# Rx_Nano_V2-1.net
KiCad netlist of a schematic drawn in EAGLE
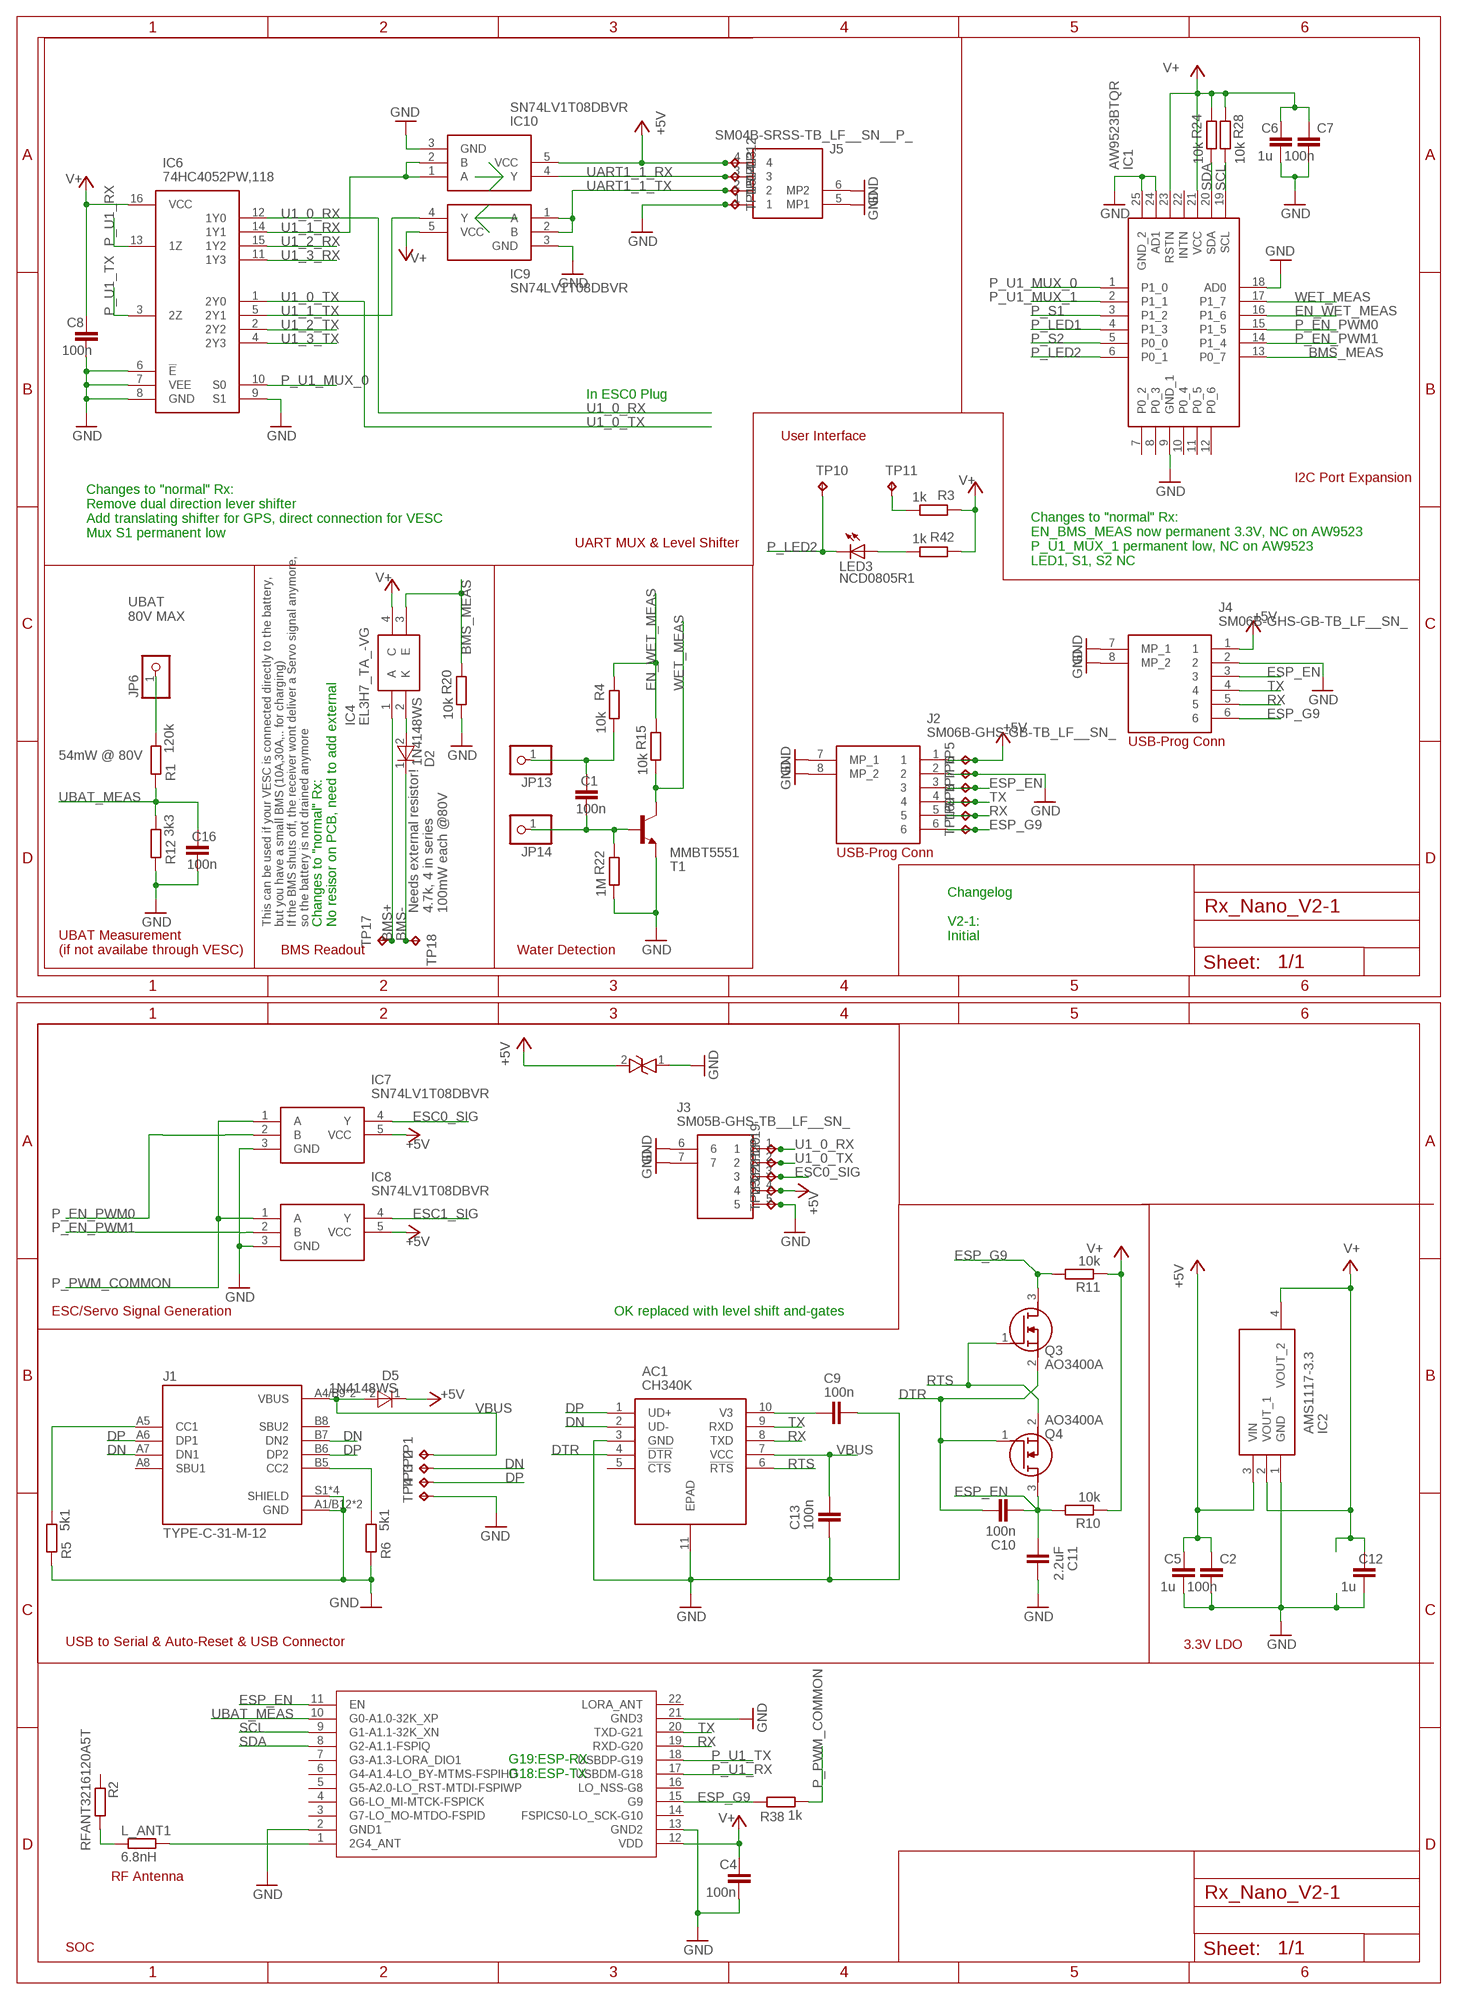
[diagram p0: schematic, sheet 1, part 1 of 2]
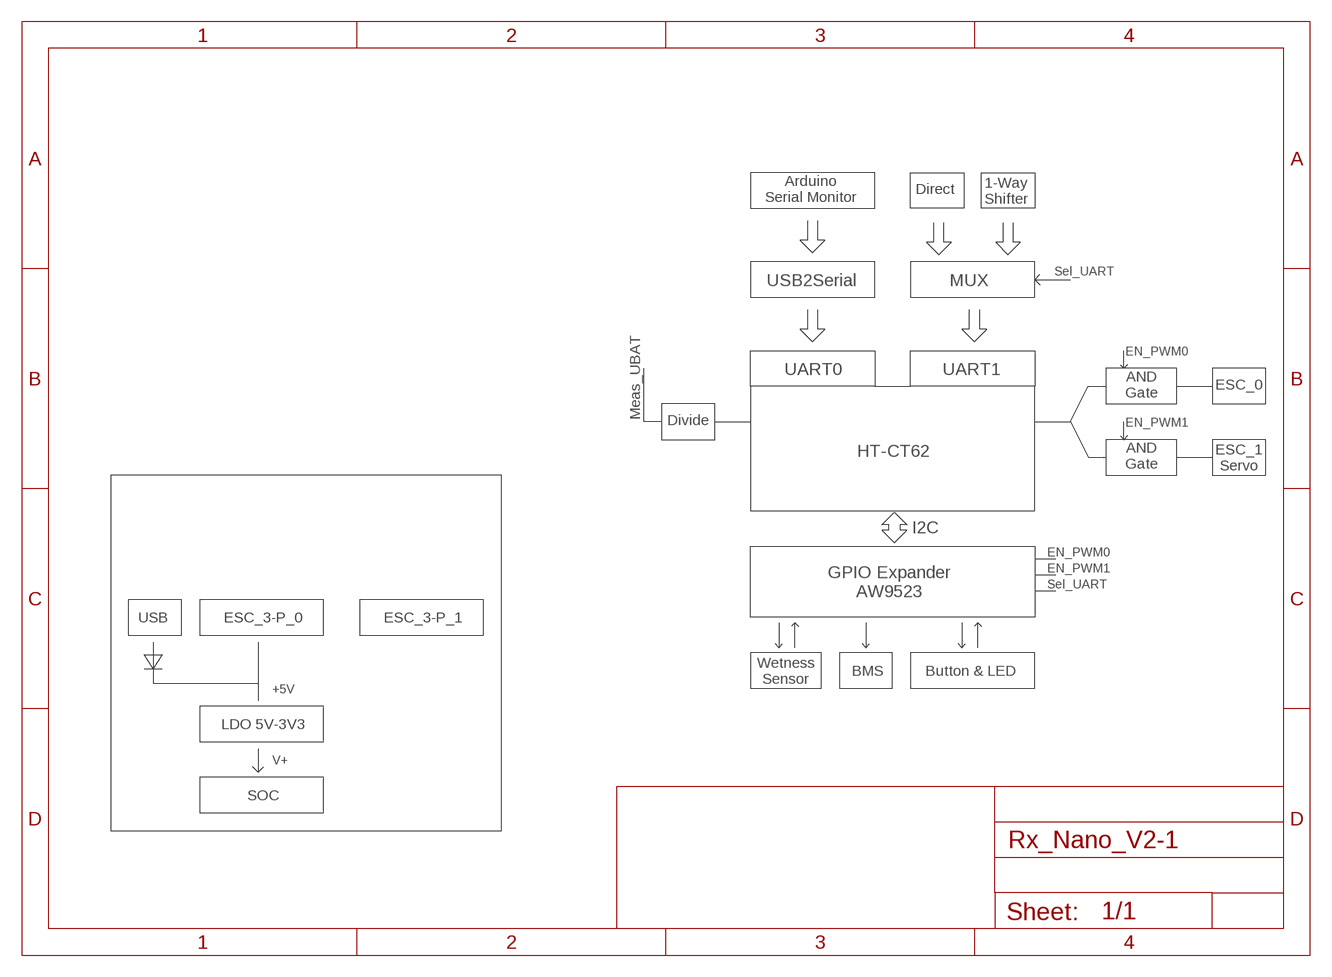
[diagram p1: schematic, sheet 1, part 2 of 2]

(export (version "E")
  (design (tool "Eeschema 10.0.6"))
  (components
    (comp (ref "AC1")
      (value "CH340K")
      (footprint "eagle-import:SOP100P600X180-11N")
      (libsource (lib "eagle-import") (part "CH340K"))
    )
    (comp (ref "C1")
      (value "100n")
      (footprint "eagle-import:C0402")
      (libsource (lib "eagle-import") (part "C-EUC0402"))
    )
    (comp (ref "C2")
      (value "100n")
      (footprint "eagle-import:C0402")
      (libsource (lib "eagle-import") (part "C-EUC0402"))
    )
    (comp (ref "C4")
      (value "100n")
      (footprint "eagle-import:C0402")
      (libsource (lib "eagle-import") (part "C-EUC0402"))
    )
    (comp (ref "C5")
      (value "1u")
      (footprint "eagle-import:C0603")
      (libsource (lib "eagle-import") (part "C-EUC0603"))
    )
    (comp (ref "C6")
      (value "1u")
      (footprint "eagle-import:C0603")
      (libsource (lib "eagle-import") (part "C-EUC0603"))
    )
    (comp (ref "C7")
      (value "100n")
      (footprint "eagle-import:C0402")
      (libsource (lib "eagle-import") (part "C-EUC0402"))
    )
    (comp (ref "C8")
      (value "100n")
      (footprint "eagle-import:C0402")
      (libsource (lib "eagle-import") (part "C-EUC0402"))
    )
    (comp (ref "C9")
      (value "100n")
      (footprint "eagle-import:C0402")
      (libsource (lib "eagle-import") (part "C-EUC0402"))
    )
    (comp (ref "C10")
      (value "100n")
      (footprint "eagle-import:C0402")
      (libsource (lib "eagle-import") (part "C-EUC0402"))
    )
    (comp (ref "C11")
      (value "2.2uF")
      (footprint "eagle-import:C0603")
      (libsource (lib "eagle-import") (part "C-EUC0603"))
    )
    (comp (ref "C12")
      (value "1u")
      (footprint "eagle-import:C0603")
      (libsource (lib "eagle-import") (part "C-EUC0603"))
    )
    (comp (ref "C13")
      (value "100n")
      (footprint "eagle-import:C0402")
      (libsource (lib "eagle-import") (part "C-EUC0402"))
    )
    (comp (ref "C16")
      (value "100n")
      (footprint "eagle-import:C0402")
      (libsource (lib "eagle-import") (part "C-EUC0402"))
    )
    (comp (ref "D2")
      (value "1N4148WS")
      (footprint "eagle-import:SODFL2512X90N")
      (fields (field (name "MOUSER_PART_NUMBER") "512-1N4148WS"))
      (libsource (lib "eagle-import") (part "1N4148WS"))
    )
    (comp (ref "D4")
      (value "P6SMB6.8CA")
      (footprint "eagle-import:DIONM5436X261N")
      (fields (field (name "MOUSER_PART_NUMBER") "576-P6SMB6.8CA"))
      (libsource (lib "eagle-import") (part "P6SMB6.8CA"))
    )
    (comp (ref "D5")
      (value "1N4148WS")
      (footprint "eagle-import:SODFL2512X90N")
      (fields (field (name "MOUSER_PART_NUMBER") "512-1N4148WS"))
      (libsource (lib "eagle-import") (part "1N4148WS"))
    )
    (comp (ref "IC1")
      (value "AW9523BTQR")
      (footprint "eagle-import:QFN50P400X400X80-25N")
      (libsource (lib "eagle-import") (part "AW9523BTQR"))
    )
    (comp (ref "IC2")
      (value "AMS1117-3.3")
      (footprint "eagle-import:SOT229P700X180-4N")
      (libsource (lib "eagle-import") (part "AMS1117-3.3"))
    )
    (comp (ref "IC4")
      (value "EL3H7_TA_-VG")
      (footprint "eagle-import:SOIC127P700X200-4N")
      (fields
        (field (name "ARROW_PART_NUMBER") "EL3H7(TA)-VG")
        (field (name "MOUSER_PART_NUMBER") "638-EL3H7TAVG")
      )
      (libsource (lib "eagle-import") (part "EL3H7_TA_-VG"))
    )
    (comp (ref "IC6")
      (value "74HC4052PW,118")
      (footprint "eagle-import:SOP65P640X110-16N")
      (fields (field (name "MOUSER_PART_NUMBER") "771-74HC4052PW-T"))
      (libsource (lib "eagle-import") (part "74HC4052PW,118"))
    )
    (comp (ref "IC7")
      (value "SN74LV1T08DBVR")
      (footprint "eagle-import:SOT95P280X145-5N")
      (fields (field (name "MOUSER_PART_NUMBER") "595-SN74LV1T08DBVR"))
      (libsource (lib "eagle-import") (part "SN74LV1T08DBVR"))
    )
    (comp (ref "IC8")
      (value "SN74LV1T08DBVR")
      (footprint "eagle-import:SOT95P280X145-5N")
      (fields (field (name "MOUSER_PART_NUMBER") "595-SN74LV1T08DBVR"))
      (libsource (lib "eagle-import") (part "SN74LV1T08DBVR"))
    )
    (comp (ref "IC9")
      (value "SN74LV1T08DBVR")
      (footprint "eagle-import:SOT95P280X145-5N")
      (fields (field (name "MOUSER_PART_NUMBER") "595-SN74LV1T08DBVR"))
      (libsource (lib "eagle-import") (part "SN74LV1T08DBVR"))
    )
    (comp (ref "IC10")
      (value "SN74LV1T08DBVR")
      (footprint "eagle-import:SOT95P280X145-5N")
      (fields (field (name "MOUSER_PART_NUMBER") "595-SN74LV1T08DBVR"))
      (libsource (lib "eagle-import") (part "SN74LV1T08DBVR"))
    )
    (comp (ref "J1")
      (value "TYPE-C-31-M-12")
      (footprint "eagle-import:HRO_TYPE-C-31-M-12")
      (fields (field (name "MF") "HRO Electronics Co., Ltd."))
      (libsource (lib "eagle-import") (part "TYPE-C-31-M-12"))
    )
    (comp (ref "J2")
      (value "SM06B-GHS-GB-TB_LF__SN_")
      (footprint "eagle-import:SM06BGHSGBTBLFSN")
      (fields
        (field (name "MANUFACTURER_PART_NUMBER") "SM06B-GHS-GB-TB(LF)(SN)")
        (field (name "MOUSER_PART_NUMBER") "306-SM06BGHSGBTBLFSN")
      )
      (libsource (lib "eagle-import") (part "SM06B-GHS-GB-TB_LF__SN_"))
    )
    (comp (ref "J3")
      (value "SM05B-GHS-TB__LF__SN_")
      (footprint "eagle-import:SM05BGHSTBLFSN")
      (fields (field (name "MANUFACTURER_PART_NUMBER") "SM05B-GHS-TB (LF)(SN)"))
      (libsource (lib "eagle-import") (part "SM05B-GHS-TB__LF__SN_"))
    )
    (comp (ref "J4")
      (value "SM06B-GHS-GB-TB_LF__SN_")
      (footprint "eagle-import:SM06BGHSGBTBLFSN")
      (fields
        (field (name "MANUFACTURER_PART_NUMBER") "SM06B-GHS-GB-TB(LF)(SN)")
        (field (name "MOUSER_PART_NUMBER") "306-SM06BGHSGBTBLFSN")
      )
      (libsource (lib "eagle-import") (part "SM06B-GHS-GB-TB_LF__SN_"))
    )
    (comp (ref "J5")
      (value "SM04B-SRSS-TB_LF__SN__P_")
      (footprint "eagle-import:SM04BSRSSTBLFSNP")
      (fields
        (field (name "MANUFACTURER_PART_NUMBER") "SM04B-SRSS-TB(LF)(SN)(P)")
        (field (name "MOUSER_PART_NUMBER") "306-SM04BSRSSTBLFSNP")
      )
      (libsource (lib "eagle-import") (part "SM04B-SRSS-TB_LF__SN__P_"))
    )
    (comp (ref "JP6")
      (value "PINHD-1X1")
      (footprint "eagle-import:1X01")
      (libsource (lib "eagle-import") (part "PINHD-1X1"))
    )
    (comp (ref "JP13")
      (value "PINHD-1X1")
      (footprint "eagle-import:1X01")
      (libsource (lib "eagle-import") (part "PINHD-1X1"))
    )
    (comp (ref "JP14")
      (value "PINHD-1X1")
      (footprint "eagle-import:1X01")
      (libsource (lib "eagle-import") (part "PINHD-1X1"))
    )
    (comp (ref "LED3")
      (value "NCD0805R1")
      (footprint "eagle-import:CHIP-LED0603")
      (libsource (lib "eagle-import") (part "LEDCHIP-LED0603"))
    )
    (comp (ref "L_ANT1")
      (value "6.8nH")
      (footprint "eagle-import:R0402")
      (libsource (lib "eagle-import") (part "R-EU_R0402"))
    )
    (comp (ref "Q3")
      (value "AO3400A")
      (footprint "eagle-import:SOT95P280X125-3N")
      (libsource (lib "eagle-import") (part "AO3400A"))
    )
    (comp (ref "Q4")
      (value "AO3400A")
      (footprint "eagle-import:SOT95P280X125-3N")
      (libsource (lib "eagle-import") (part "AO3400A"))
    )
    (comp (ref "R1")
      (value "120k")
      (footprint "eagle-import:R0603")
      (libsource (lib "eagle-import") (part "R-EU_R0603"))
    )
    (comp (ref "R2")
      (value "RFANT3216120A5T")
      (footprint "eagle-import:R1206")
      (libsource (lib "eagle-import") (part "R-EU_R1206"))
    )
    (comp (ref "R3")
      (value "1k")
      (footprint "eagle-import:R0402")
      (libsource (lib "eagle-import") (part "R-EU_R0402"))
    )
    (comp (ref "R4")
      (value "10k")
      (footprint "eagle-import:R0402")
      (libsource (lib "eagle-import") (part "R-EU_R0402"))
    )
    (comp (ref "R5")
      (value "5k1")
      (footprint "eagle-import:R0402")
      (libsource (lib "eagle-import") (part "R-EU_R0402"))
    )
    (comp (ref "R6")
      (value "5k1")
      (footprint "eagle-import:R0402")
      (libsource (lib "eagle-import") (part "R-EU_R0402"))
    )
    (comp (ref "R10")
      (value "10k")
      (footprint "eagle-import:R0402")
      (libsource (lib "eagle-import") (part "R-EU_R0402"))
    )
    (comp (ref "R11")
      (value "10k")
      (footprint "eagle-import:R0402")
      (libsource (lib "eagle-import") (part "R-EU_R0402"))
    )
    (comp (ref "R12")
      (value "3k3")
      (footprint "eagle-import:R0402")
      (libsource (lib "eagle-import") (part "R-EU_R0402"))
    )
    (comp (ref "R15")
      (value "10k")
      (footprint "eagle-import:R0402")
      (libsource (lib "eagle-import") (part "R-EU_R0402"))
    )
    (comp (ref "R20")
      (value "10k")
      (footprint "eagle-import:R0402")
      (libsource (lib "eagle-import") (part "R-EU_R0402"))
    )
    (comp (ref "R22")
      (value "1M")
      (footprint "eagle-import:R0402")
      (libsource (lib "eagle-import") (part "R-EU_R0402"))
    )
    (comp (ref "R24")
      (value "10k")
      (footprint "eagle-import:R0402")
      (libsource (lib "eagle-import") (part "R-EU_R0402"))
    )
    (comp (ref "R28")
      (value "10k")
      (footprint "eagle-import:R0402")
      (libsource (lib "eagle-import") (part "R-EU_R0402"))
    )
    (comp (ref "R38")
      (value "1k")
      (footprint "eagle-import:R0402")
      (libsource (lib "eagle-import") (part "R-EU_R0402"))
    )
    (comp (ref "R42")
      (value "1k")
      (footprint "eagle-import:R0402")
      (libsource (lib "eagle-import") (part "R-EU_R0402"))
    )
    (comp (ref "T1")
      (value "MMBT5551")
      (footprint "eagle-import:SOT23-BEC")
      (libsource (lib "eagle-import") (part "-NPN-SOT23-BECBC847B"))
    )
    (comp (ref "TP1")
      (value "TPB1,27")
      (footprint "eagle-import:B1,27")
      (libsource (lib "eagle-import") (part "TPB1,27"))
    )
    (comp (ref "TP2")
      (value "TPB1,27")
      (footprint "eagle-import:B1,27")
      (libsource (lib "eagle-import") (part "TPB1,27"))
    )
    (comp (ref "TP3")
      (value "TPB1,27")
      (footprint "eagle-import:B1,27")
      (libsource (lib "eagle-import") (part "TPB1,27"))
    )
    (comp (ref "TP4")
      (value "TPB1,27")
      (footprint "eagle-import:B1,27")
      (libsource (lib "eagle-import") (part "TPB1,27"))
    )
    (comp (ref "TP5")
      (value "TPB1,27")
      (footprint "eagle-import:B1,27")
      (libsource (lib "eagle-import") (part "TPB1,27"))
    )
    (comp (ref "TP6")
      (value "TPB1,27")
      (footprint "eagle-import:B1,27")
      (libsource (lib "eagle-import") (part "TPB1,27"))
    )
    (comp (ref "TP7")
      (value "TPB1,27")
      (footprint "eagle-import:B1,27")
      (libsource (lib "eagle-import") (part "TPB1,27"))
    )
    (comp (ref "TP8")
      (value "TPB1,27")
      (footprint "eagle-import:B1,27")
      (libsource (lib "eagle-import") (part "TPB1,27"))
    )
    (comp (ref "TP9")
      (value "TPB1,27")
      (footprint "eagle-import:B1,27")
      (libsource (lib "eagle-import") (part "TPB1,27"))
    )
    (comp (ref "TP10")
      (value "TPB1,27")
      (footprint "eagle-import:B1,27")
      (libsource (lib "eagle-import") (part "TPB1,27"))
    )
    (comp (ref "TP11")
      (value "TPB1,27")
      (footprint "eagle-import:B1,27")
      (libsource (lib "eagle-import") (part "TPB1,27"))
    )
    (comp (ref "TP12")
      (value "TPB1,27")
      (footprint "eagle-import:B1,27")
      (libsource (lib "eagle-import") (part "TPB1,27"))
    )
    (comp (ref "TP13")
      (value "TPB1,27")
      (footprint "eagle-import:B1,27")
      (libsource (lib "eagle-import") (part "TPB1,27"))
    )
    (comp (ref "TP14")
      (value "TPB1,27")
      (footprint "eagle-import:B1,27")
      (libsource (lib "eagle-import") (part "TPB1,27"))
    )
    (comp (ref "TP15")
      (value "TPB1,27")
      (footprint "eagle-import:B1,27")
      (libsource (lib "eagle-import") (part "TPB1,27"))
    )
    (comp (ref "TP16")
      (value "TPB1,27")
      (footprint "eagle-import:B1,27")
      (libsource (lib "eagle-import") (part "TPB1,27"))
    )
    (comp (ref "TP17")
      (value "TPB1,27")
      (footprint "eagle-import:B1,27")
      (libsource (lib "eagle-import") (part "TPB1,27"))
    )
    (comp (ref "TP18")
      (value "TPB1,27")
      (footprint "eagle-import:B1,27")
      (libsource (lib "eagle-import") (part "TPB1,27"))
    )
    (comp (ref "TP19")
      (value "TPB1,27")
      (footprint "eagle-import:B1,27")
      (libsource (lib "eagle-import") (part "TPB1,27"))
    )
    (comp (ref "TP20")
      (value "TPB1,27")
      (footprint "eagle-import:B1,27")
      (libsource (lib "eagle-import") (part "TPB1,27"))
    )
    (comp (ref "TP21")
      (value "TPB1,27")
      (footprint "eagle-import:B1,27")
      (libsource (lib "eagle-import") (part "TPB1,27"))
    )
    (comp (ref "TP22")
      (value "TPB1,27")
      (footprint "eagle-import:B1,27")
      (libsource (lib "eagle-import") (part "TPB1,27"))
    )
    (comp (ref "TP23")
      (value "TPB1,27")
      (footprint "eagle-import:B1,27")
      (libsource (lib "eagle-import") (part "TPB1,27"))
    )
    (comp (ref "U$5")
      (value "HT-CT62")
      (footprint "eagle-import:HT-CT62")
      (libsource (lib "eagle-import") (part "HT-CT62"))
    )
  )
  (nets
    (net (code "1") (name "+5V") (class "Default")
      (node (ref "C2") (pin "1") (pinfunction "1_1") (pintype "passive"))
      (node (ref "C5") (pin "1") (pinfunction "1_1") (pintype "passive"))
      (node (ref "D4") (pin "2") (pinfunction "2_2") (pintype "bidirectional"))
      (node (ref "D5") (pin "1") (pinfunction "K_1") (pintype "bidirectional"))
      (node (ref "IC10") (pin "5") (pinfunction "VCC_5") (pintype "power_in"))
      (node (ref "IC2") (pin "3") (pinfunction "VIN_3") (pintype "bidirectional"))
      (node (ref "IC7") (pin "5") (pinfunction "VCC_5") (pintype "power_in"))
      (node (ref "IC8") (pin "5") (pinfunction "VCC_5") (pintype "power_in"))
      (node (ref "J2") (pin "1") (pinfunction "1_1") (pintype "bidirectional"))
      (node (ref "J3") (pin "4") (pinfunction "4_4") (pintype "bidirectional"))
      (node (ref "J4") (pin "1") (pinfunction "1_1") (pintype "bidirectional"))
      (node (ref "J5") (pin "4") (pinfunction "4_4") (pintype "bidirectional"))
      (node (ref "TP12") (pin "TP") (pinfunction "TP_TP") (pintype "input"))
      (node (ref "TP22") (pin "TP") (pinfunction "TP_TP") (pintype "input"))
      (node (ref "TP5") (pin "TP") (pinfunction "TP_TP") (pintype "input"))
    )
    (net (code "2") (name "/BMS+") (class "Default")
      (node (ref "IC4") (pin "1") (pinfunction "A_1") (pintype "bidirectional"))
      (node (ref "TP17") (pin "TP") (pinfunction "TP_TP") (pintype "input"))
    )
    (net (code "3") (name "/BMS-") (class "Default")
      (node (ref "D2") (pin "1") (pinfunction "K_1") (pintype "bidirectional"))
      (node (ref "TP18") (pin "TP") (pinfunction "TP_TP") (pintype "input"))
    )
    (net (code "4") (name "/BMS_MEAS") (class "Default")
      (node (ref "IC1") (pin "13") (pinfunction "P0_7_13") (pintype "bidirectional"))
      (node (ref "IC4") (pin "3") (pinfunction "E_3") (pintype "bidirectional"))
      (node (ref "R20") (pin "1") (pinfunction "1_1") (pintype "passive"))
    )
    (net (code "5") (name "/DN") (class "Default")
      (node (ref "AC1") (pin "2") (pinfunction "UD-_2") (pintype "bidirectional"))
      (node (ref "J1") (pin "A7") (pinfunction "DN1_A7") (pintype "bidirectional"))
      (node (ref "J1") (pin "B7") (pinfunction "DN2_B7") (pintype "bidirectional"))
      (node (ref "TP2") (pin "TP") (pinfunction "TP_TP") (pintype "input"))
    )
    (net (code "6") (name "/DP") (class "Default")
      (node (ref "AC1") (pin "1") (pinfunction "UD+_1") (pintype "bidirectional"))
      (node (ref "J1") (pin "A6") (pinfunction "DP1_A6") (pintype "bidirectional"))
      (node (ref "J1") (pin "B6") (pinfunction "DP2_B6") (pintype "bidirectional"))
      (node (ref "TP3") (pin "TP") (pinfunction "TP_TP") (pintype "input"))
    )
    (net (code "7") (name "/DTR") (class "Default")
      (node (ref "AC1") (pin "4") (pinfunction "~{DTR}_4") (pintype "bidirectional"))
      (node (ref "C10") (pin "1") (pinfunction "1_1") (pintype "passive"))
      (node (ref "Q3") (pin "2") (pinfunction "S_2") (pintype "bidirectional"))
      (node (ref "Q4") (pin "1") (pinfunction "G_1") (pintype "bidirectional"))
    )
    (net (code "8") (name "/EN_WET_MEAS") (class "Default")
      (node (ref "IC1") (pin "16") (pinfunction "P1_6_16") (pintype "bidirectional"))
      (node (ref "R15") (pin "1") (pinfunction "1_1") (pintype "passive"))
      (node (ref "R4") (pin "1") (pinfunction "1_1") (pintype "passive"))
    )
    (net (code "9") (name "/ESC0_SIG") (class "Default")
      (node (ref "IC7") (pin "4") (pinfunction "Y_4") (pintype "output"))
      (node (ref "J3") (pin "3") (pinfunction "3_3") (pintype "bidirectional"))
      (node (ref "TP21") (pin "TP") (pinfunction "TP_TP") (pintype "input"))
    )
    (net (code "10") (name "/ESC1_SIG") (class "Default")
      (node (ref "IC8") (pin "4") (pinfunction "Y_4") (pintype "output"))
    )
    (net (code "11") (name "/ESP_EN") (class "Default")
      (node (ref "C10") (pin "2") (pinfunction "2_2") (pintype "passive"))
      (node (ref "C11") (pin "2") (pinfunction "2_2") (pintype "passive"))
      (node (ref "J2") (pin "3") (pinfunction "3_3") (pintype "bidirectional"))
      (node (ref "J4") (pin "3") (pinfunction "3_3") (pintype "bidirectional"))
      (node (ref "Q4") (pin "3") (pinfunction "D_3") (pintype "bidirectional"))
      (node (ref "R10") (pin "2") (pinfunction "2_2") (pintype "passive"))
      (node (ref "TP7") (pin "TP") (pinfunction "TP_TP") (pintype "input"))
      (node (ref "U$5") (pin "11") (pinfunction "EN_11") (pintype "bidirectional"))
    )
    (net (code "12") (name "/ESP_G9") (class "Default")
      (node (ref "J2") (pin "6") (pinfunction "6_6") (pintype "bidirectional"))
      (node (ref "J4") (pin "6") (pinfunction "6_6") (pintype "bidirectional"))
      (node (ref "Q3") (pin "3") (pinfunction "D_3") (pintype "bidirectional"))
      (node (ref "R11") (pin "2") (pinfunction "2_2") (pintype "passive"))
      (node (ref "R38") (pin "1") (pinfunction "1_1") (pintype "passive"))
      (node (ref "TP16") (pin "TP") (pinfunction "TP_TP") (pintype "input"))
      (node (ref "U$5") (pin "15") (pinfunction "G9_15") (pintype "bidirectional"))
    )
    (net (code "13") (name "/P_EN_PWM0") (class "Default")
      (node (ref "IC1") (pin "15") (pinfunction "P1_5_15") (pintype "bidirectional"))
      (node (ref "IC7") (pin "2") (pinfunction "B_2") (pintype "input"))
    )
    (net (code "14") (name "/P_EN_PWM1") (class "Default")
      (node (ref "IC1") (pin "14") (pinfunction "P1_4_14") (pintype "bidirectional"))
      (node (ref "IC8") (pin "2") (pinfunction "B_2") (pintype "input"))
    )
    (net (code "15") (name "/P_LED1") (class "Default")
      (node (ref "IC1") (pin "4") (pinfunction "P1_3_4") (pintype "bidirectional"))
    )
    (net (code "16") (name "/P_LED2") (class "Default")
      (node (ref "IC1") (pin "6") (pinfunction "P0_1_6") (pintype "bidirectional"))
      (node (ref "LED3") (pin "C") (pinfunction "C_C") (pintype "passive"))
      (node (ref "TP10") (pin "TP") (pinfunction "TP_TP") (pintype "input"))
    )
    (net (code "17") (name "/P_PWM_COMMON") (class "Default")
      (node (ref "IC7") (pin "1") (pinfunction "A_1") (pintype "input"))
      (node (ref "IC8") (pin "1") (pinfunction "A_1") (pintype "input"))
      (node (ref "R38") (pin "2") (pinfunction "2_2") (pintype "passive"))
    )
    (net (code "18") (name "/P_S1") (class "Default")
      (node (ref "IC1") (pin "3") (pinfunction "P1_2_3") (pintype "bidirectional"))
    )
    (net (code "19") (name "/P_S2") (class "Default")
      (node (ref "IC1") (pin "5") (pinfunction "P0_0_5") (pintype "bidirectional"))
    )
    (net (code "20") (name "/P_U1_MUX_0") (class "Default")
      (node (ref "IC1") (pin "1") (pinfunction "P1_0_1") (pintype "bidirectional"))
      (node (ref "IC6") (pin "10") (pinfunction "S0_10") (pintype "bidirectional"))
    )
    (net (code "21") (name "/P_U1_MUX_1") (class "Default")
      (node (ref "IC1") (pin "2") (pinfunction "P1_1_2") (pintype "bidirectional"))
    )
    (net (code "22") (name "/P_U1_RX") (class "Default")
      (node (ref "IC6") (pin "13") (pinfunction "1Z_13") (pintype "bidirectional"))
      (node (ref "U$5") (pin "17") (pinfunction "USBDM-G18_17") (pintype "bidirectional"))
    )
    (net (code "23") (name "/P_U1_TX") (class "Default")
      (node (ref "IC6") (pin "3") (pinfunction "2Z_3") (pintype "bidirectional"))
      (node (ref "U$5") (pin "18") (pinfunction "USBDP-G19_18") (pintype "bidirectional"))
    )
    (net (code "24") (name "/RTS") (class "Default")
      (node (ref "AC1") (pin "6") (pinfunction "~{RTS}_6") (pintype "bidirectional"))
      (node (ref "Q3") (pin "1") (pinfunction "G_1") (pintype "bidirectional"))
      (node (ref "Q4") (pin "2") (pinfunction "S_2") (pintype "bidirectional"))
    )
    (net (code "25") (name "/RX") (class "Default")
      (node (ref "AC1") (pin "8") (pinfunction "TXD_8") (pintype "bidirectional"))
      (node (ref "J2") (pin "5") (pinfunction "5_5") (pintype "bidirectional"))
      (node (ref "J4") (pin "5") (pinfunction "5_5") (pintype "bidirectional"))
      (node (ref "TP9") (pin "TP") (pinfunction "TP_TP") (pintype "input"))
      (node (ref "U$5") (pin "19") (pinfunction "RXD-G20_19") (pintype "bidirectional"))
    )
    (net (code "26") (name "/SCL") (class "Default")
      (node (ref "IC1") (pin "19") (pinfunction "SCL_19") (pintype "bidirectional"))
      (node (ref "R28") (pin "2") (pinfunction "2_2") (pintype "passive"))
      (node (ref "U$5") (pin "9") (pinfunction "G1-A1.1-32K_XN_9") (pintype "bidirectional"))
    )
    (net (code "27") (name "/SDA") (class "Default")
      (node (ref "IC1") (pin "20") (pinfunction "SDA_20") (pintype "bidirectional"))
      (node (ref "R24") (pin "2") (pinfunction "2_2") (pintype "passive"))
      (node (ref "U$5") (pin "8") (pinfunction "G2-A1.1-FSPIQ_8") (pintype "bidirectional"))
    )
    (net (code "28") (name "/TX") (class "Default")
      (node (ref "AC1") (pin "9") (pinfunction "RXD_9") (pintype "bidirectional"))
      (node (ref "J2") (pin "4") (pinfunction "4_4") (pintype "bidirectional"))
      (node (ref "J4") (pin "4") (pinfunction "4_4") (pintype "bidirectional"))
      (node (ref "TP8") (pin "TP") (pinfunction "TP_TP") (pintype "input"))
      (node (ref "U$5") (pin "20") (pinfunction "TXD-G21_20") (pintype "bidirectional"))
    )
    (net (code "29") (name "/U1_0_RX") (class "Default")
      (node (ref "IC6") (pin "12") (pinfunction "1Y0_12") (pintype "bidirectional"))
      (node (ref "J3") (pin "1") (pinfunction "1_1") (pintype "bidirectional"))
      (node (ref "TP19") (pin "TP") (pinfunction "TP_TP") (pintype "input"))
    )
    (net (code "30") (name "/U1_0_TX") (class "Default")
      (node (ref "IC6") (pin "1") (pinfunction "2Y0_1") (pintype "bidirectional"))
      (node (ref "J3") (pin "2") (pinfunction "2_2") (pintype "bidirectional"))
      (node (ref "TP20") (pin "TP") (pinfunction "TP_TP") (pintype "input"))
    )
    (net (code "31") (name "/U1_1_RX") (class "Default")
      (node (ref "IC10") (pin "1") (pinfunction "A_1") (pintype "input"))
      (node (ref "IC10") (pin "2") (pinfunction "B_2") (pintype "input"))
      (node (ref "IC6") (pin "14") (pinfunction "1Y1_14") (pintype "bidirectional"))
    )
    (net (code "32") (name "/U1_1_TX") (class "Default")
      (node (ref "IC6") (pin "5") (pinfunction "2Y1_5") (pintype "bidirectional"))
      (node (ref "IC9") (pin "4") (pinfunction "Y_4") (pintype "output"))
    )
    (net (code "33") (name "/U1_2_RX") (class "Default")
      (node (ref "IC6") (pin "15") (pinfunction "1Y2_15") (pintype "bidirectional"))
    )
    (net (code "34") (name "/U1_2_TX") (class "Default")
      (node (ref "IC6") (pin "2") (pinfunction "2Y2_2") (pintype "bidirectional"))
    )
    (net (code "35") (name "/U1_3_RX") (class "Default")
      (node (ref "IC6") (pin "11") (pinfunction "1Y3_11") (pintype "bidirectional"))
    )
    (net (code "36") (name "/U1_3_TX") (class "Default")
      (node (ref "IC6") (pin "4") (pinfunction "2Y3_4") (pintype "bidirectional"))
    )
    (net (code "37") (name "/UART1_1_RX") (class "Default")
      (node (ref "IC10") (pin "4") (pinfunction "Y_4") (pintype "output"))
      (node (ref "J5") (pin "3") (pinfunction "3_3") (pintype "bidirectional"))
      (node (ref "TP13") (pin "TP") (pinfunction "TP_TP") (pintype "input"))
    )
    (net (code "38") (name "/UART1_1_TX") (class "Default")
      (node (ref "IC9") (pin "1") (pinfunction "A_1") (pintype "input"))
      (node (ref "IC9") (pin "2") (pinfunction "B_2") (pintype "input"))
      (node (ref "J5") (pin "2") (pinfunction "2_2") (pintype "bidirectional"))
      (node (ref "TP14") (pin "TP") (pinfunction "TP_TP") (pintype "input"))
    )
    (net (code "39") (name "/UBAT_MEAS") (class "Default")
      (node (ref "C16") (pin "1") (pinfunction "1_1") (pintype "passive"))
      (node (ref "R1") (pin "1") (pinfunction "1_1") (pintype "passive"))
      (node (ref "R12") (pin "2") (pinfunction "2_2") (pintype "passive"))
      (node (ref "U$5") (pin "10") (pinfunction "G0-A1.0-32K_XP_10") (pintype "bidirectional"))
    )
    (net (code "40") (name "/VBUS") (class "Default")
      (node (ref "AC1") (pin "7") (pinfunction "VCC_7") (pintype "power_in"))
      (node (ref "C13") (pin "1") (pinfunction "1_1") (pintype "passive"))
      (node (ref "D5") (pin "2") (pinfunction "A_2") (pintype "bidirectional"))
      (node (ref "J1") (pin "A4/B9") (pinfunction "VBUS_A4/B9") (pintype "power_in"))
      (node (ref "J1") (pin "B4/A9") (pinfunction "VBUS_B4/A9") (pintype "power_in"))
      (node (ref "TP1") (pin "TP") (pinfunction "TP_TP") (pintype "input"))
    )
    (net (code "41") (name "/WET_MEAS") (class "Default")
      (node (ref "IC1") (pin "17") (pinfunction "P1_7_17") (pintype "bidirectional"))
      (node (ref "R15") (pin "2") (pinfunction "2_2") (pintype "passive"))
      (node (ref "T1") (pin "C") (pinfunction "C_C") (pintype "passive"))
    )
    (net (code "42") (name "GND") (class "Default")
      (node (ref "AC1") (pin "11") (pinfunction "EPAD_11") (pintype "power_in"))
      (node (ref "AC1") (pin "3") (pinfunction "GND_3") (pintype "power_in"))
      (node (ref "C11") (pin "1") (pinfunction "1_1") (pintype "passive"))
      (node (ref "C12") (pin "2") (pinfunction "2_2") (pintype "passive"))
      (node (ref "C13") (pin "2") (pinfunction "2_2") (pintype "passive"))
      (node (ref "C16") (pin "2") (pinfunction "2_2") (pintype "passive"))
      (node (ref "C2") (pin "2") (pinfunction "2_2") (pintype "passive"))
      (node (ref "C4") (pin "2") (pinfunction "2_2") (pintype "passive"))
      (node (ref "C5") (pin "2") (pinfunction "2_2") (pintype "passive"))
      (node (ref "C6") (pin "2") (pinfunction "2_2") (pintype "passive"))
      (node (ref "C7") (pin "2") (pinfunction "2_2") (pintype "passive"))
      (node (ref "C8") (pin "2") (pinfunction "2_2") (pintype "passive"))
      (node (ref "C9") (pin "1") (pinfunction "1_1") (pintype "passive"))
      (node (ref "D4") (pin "1") (pinfunction "1_1") (pintype "bidirectional"))
      (node (ref "IC1") (pin "18") (pinfunction "AD0_18") (pintype "bidirectional"))
      (node (ref "IC1") (pin "24") (pinfunction "AD1_24") (pintype "bidirectional"))
      (node (ref "IC1") (pin "25") (pinfunction "GND_2_25") (pintype "bidirectional"))
      (node (ref "IC1") (pin "9") (pinfunction "GND_1_9") (pintype "bidirectional"))
      (node (ref "IC10") (pin "3") (pinfunction "GND_3") (pintype "power_in"))
      (node (ref "IC2") (pin "1") (pinfunction "GND_1") (pintype "bidirectional"))
      (node (ref "IC6") (pin "6") (pinfunction "~{E}_6") (pintype "bidirectional"))
      (node (ref "IC6") (pin "7") (pinfunction "VEE_7") (pintype "bidirectional"))
      (node (ref "IC6") (pin "8") (pinfunction "GND_8") (pintype "bidirectional"))
      (node (ref "IC6") (pin "9") (pinfunction "S1_9") (pintype "bidirectional"))
      (node (ref "IC7") (pin "3") (pinfunction "GND_3") (pintype "power_in"))
      (node (ref "IC8") (pin "3") (pinfunction "GND_3") (pintype "power_in"))
      (node (ref "IC9") (pin "3") (pinfunction "GND_3") (pintype "power_in"))
      (node (ref "J1") (pin "A1/B12") (pinfunction "GND_A1/B12") (pintype "power_in"))
      (node (ref "J1") (pin "B1/A12") (pinfunction "GND_B1/A12") (pintype "power_in"))
      (node (ref "J1") (pin "S1") (pinfunction "SHIELD_S1") (pintype "passive"))
      (node (ref "J1") (pin "S2") (pinfunction "SHIELD_S2") (pintype "passive"))
      (node (ref "J1") (pin "S3") (pinfunction "SHIELD_S3") (pintype "passive"))
      (node (ref "J1") (pin "S4") (pinfunction "SHIELD_S4") (pintype "passive"))
      (node (ref "J2") (pin "2") (pinfunction "2_2") (pintype "bidirectional"))
      (node (ref "J2") (pin "7") (pinfunction "MP_1_7") (pintype "bidirectional"))
      (node (ref "J2") (pin "8") (pinfunction "MP_2_8") (pintype "bidirectional"))
      (node (ref "J3") (pin "5") (pinfunction "5_5") (pintype "bidirectional"))
      (node (ref "J3") (pin "6") (pinfunction "6_6") (pintype "bidirectional"))
      (node (ref "J3") (pin "7") (pinfunction "7_7") (pintype "bidirectional"))
      (node (ref "J4") (pin "2") (pinfunction "2_2") (pintype "bidirectional"))
      (node (ref "J4") (pin "7") (pinfunction "MP_1_7") (pintype "bidirectional"))
      (node (ref "J4") (pin "8") (pinfunction "MP_2_8") (pintype "bidirectional"))
      (node (ref "J5") (pin "1") (pinfunction "1_1") (pintype "bidirectional"))
      (node (ref "J5") (pin "5") (pinfunction "MP1_5") (pintype "bidirectional"))
      (node (ref "J5") (pin "6") (pinfunction "MP2_6") (pintype "bidirectional"))
      (node (ref "R12") (pin "1") (pinfunction "1_1") (pintype "passive"))
      (node (ref "R20") (pin "2") (pinfunction "2_2") (pintype "passive"))
      (node (ref "R22") (pin "2") (pinfunction "2_2") (pintype "passive"))
      (node (ref "R5") (pin "1") (pinfunction "1_1") (pintype "passive"))
      (node (ref "R6") (pin "1") (pinfunction "1_1") (pintype "passive"))
      (node (ref "T1") (pin "E") (pinfunction "E_E") (pintype "passive"))
      (node (ref "TP15") (pin "TP") (pinfunction "TP_TP") (pintype "input"))
      (node (ref "TP23") (pin "TP") (pinfunction "TP_TP") (pintype "input"))
      (node (ref "TP4") (pin "TP") (pinfunction "TP_TP") (pintype "input"))
      (node (ref "TP6") (pin "TP") (pinfunction "TP_TP") (pintype "input"))
      (node (ref "U$5") (pin "13") (pinfunction "GND2_13") (pintype "bidirectional"))
      (node (ref "U$5") (pin "2") (pinfunction "GND1_2") (pintype "bidirectional"))
      (node (ref "U$5") (pin "21") (pinfunction "GND3_21") (pintype "bidirectional"))
    )
    (net (code "43") (name "Net-(AC1-V3)") (class "Default")
      (node (ref "AC1") (pin "10") (pinfunction "V3_10") (pintype "power_in"))
      (node (ref "C9") (pin "2") (pinfunction "2_2") (pintype "passive"))
    )
    (net (code "44") (name "Net-(C1-Pad1)") (class "Default")
      (node (ref "C1") (pin "1") (pinfunction "1_1") (pintype "passive"))
      (node (ref "JP13") (pin "1") (pinfunction "1_1") (pintype "passive"))
      (node (ref "R4") (pin "2") (pinfunction "2_2") (pintype "passive"))
    )
    (net (code "45") (name "Net-(C1-Pad2)") (class "Default")
      (node (ref "C1") (pin "2") (pinfunction "2_2") (pintype "passive"))
      (node (ref "JP14") (pin "1") (pinfunction "1_1") (pintype "passive"))
      (node (ref "R22") (pin "1") (pinfunction "1_1") (pintype "passive"))
      (node (ref "T1") (pin "B") (pinfunction "B_B") (pintype "passive"))
    )
    (net (code "46") (name "Net-(D2-A)") (class "Default")
      (node (ref "D2") (pin "2") (pinfunction "A_2") (pintype "bidirectional"))
      (node (ref "IC4") (pin "2") (pinfunction "K_2") (pintype "bidirectional"))
    )
    (net (code "47") (name "Net-(J1-CC1)") (class "Default")
      (node (ref "J1") (pin "A5") (pinfunction "CC1_A5") (pintype "bidirectional"))
      (node (ref "R5") (pin "2") (pinfunction "2_2") (pintype "passive"))
    )
    (net (code "48") (name "Net-(J1-CC2)") (class "Default")
      (node (ref "J1") (pin "B5") (pinfunction "CC2_B5") (pintype "bidirectional"))
      (node (ref "R6") (pin "2") (pinfunction "2_2") (pintype "passive"))
    )
    (net (code "49") (name "Net-(JP6-Pad1)") (class "Default")
      (node (ref "JP6") (pin "1") (pinfunction "1_1") (pintype "passive"))
      (node (ref "R1") (pin "2") (pinfunction "2_2") (pintype "passive"))
    )
    (net (code "50") (name "Net-(LED3-PadA)") (class "Default")
      (node (ref "LED3") (pin "A") (pinfunction "A_A") (pintype "passive"))
      (node (ref "R42") (pin "2") (pinfunction "2_2") (pintype "passive"))
    )
    (net (code "51") (name "Net-(L_ANT1-Pad2)") (class "Default")
      (node (ref "L_ANT1") (pin "2") (pinfunction "2_2") (pintype "passive"))
      (node (ref "R2") (pin "2") (pinfunction "2_2") (pintype "passive"))
    )
    (net (code "52") (name "Net-(R3-Pad2)") (class "Default")
      (node (ref "R3") (pin "2") (pinfunction "2_2") (pintype "passive"))
      (node (ref "TP11") (pin "TP") (pinfunction "TP_TP") (pintype "input"))
    )
    (net (code "53") (name "Net-(U$5-2G4_ANT)") (class "Default")
      (node (ref "L_ANT1") (pin "1") (pinfunction "1_1") (pintype "passive"))
      (node (ref "U$5") (pin "1") (pinfunction "2G4_ANT_1") (pintype "bidirectional"))
    )
    (net (code "54") (name "V+") (class "Default")
      (node (ref "C12") (pin "1") (pinfunction "1_1") (pintype "passive"))
      (node (ref "C4") (pin "1") (pinfunction "1_1") (pintype "passive"))
      (node (ref "C6") (pin "1") (pinfunction "1_1") (pintype "passive"))
      (node (ref "C7") (pin "1") (pinfunction "1_1") (pintype "passive"))
      (node (ref "C8") (pin "1") (pinfunction "1_1") (pintype "passive"))
      (node (ref "IC1") (pin "21") (pinfunction "VCC_21") (pintype "bidirectional"))
      (node (ref "IC1") (pin "23") (pinfunction "RSTN_23") (pintype "bidirectional"))
      (node (ref "IC2") (pin "2") (pinfunction "VOUT_1_2") (pintype "bidirectional"))
      (node (ref "IC2") (pin "4") (pinfunction "VOUT_2_4") (pintype "bidirectional"))
      (node (ref "IC4") (pin "4") (pinfunction "C_4") (pintype "bidirectional"))
      (node (ref "IC6") (pin "16") (pinfunction "VCC_16") (pintype "bidirectional"))
      (node (ref "IC9") (pin "5") (pinfunction "VCC_5") (pintype "power_in"))
      (node (ref "R10") (pin "1") (pinfunction "1_1") (pintype "passive"))
      (node (ref "R11") (pin "1") (pinfunction "1_1") (pintype "passive"))
      (node (ref "R24") (pin "1") (pinfunction "1_1") (pintype "passive"))
      (node (ref "R28") (pin "1") (pinfunction "1_1") (pintype "passive"))
      (node (ref "R3") (pin "1") (pinfunction "1_1") (pintype "passive"))
      (node (ref "R42") (pin "1") (pinfunction "1_1") (pintype "passive"))
      (node (ref "U$5") (pin "12") (pinfunction "VDD_12") (pintype "bidirectional"))
    )
    (net (code "55") (name "unconnected-(AC1-~{CTS}-Pad5)") (class "Default")
      (node (ref "AC1") (pin "5") (pinfunction "~{CTS}_5") (pintype "bidirectional"))
    )
    (net (code "56") (name "unconnected-(IC1-INTN-Pad22)") (class "Default")
      (node (ref "IC1") (pin "22") (pinfunction "INTN_22") (pintype "bidirectional"))
    )
    (net (code "57") (name "unconnected-(IC1-P0_2-Pad7)") (class "Default")
      (node (ref "IC1") (pin "7") (pinfunction "P0_2_7") (pintype "bidirectional"))
    )
    (net (code "58") (name "unconnected-(IC1-P0_3-Pad8)") (class "Default")
      (node (ref "IC1") (pin "8") (pinfunction "P0_3_8") (pintype "bidirectional"))
    )
    (net (code "59") (name "unconnected-(IC1-P0_4-Pad10)") (class "Default")
      (node (ref "IC1") (pin "10") (pinfunction "P0_4_10") (pintype "bidirectional"))
    )
    (net (code "60") (name "unconnected-(IC1-P0_5-Pad11)") (class "Default")
      (node (ref "IC1") (pin "11") (pinfunction "P0_5_11") (pintype "bidirectional"))
    )
    (net (code "61") (name "unconnected-(IC1-P0_6-Pad12)") (class "Default")
      (node (ref "IC1") (pin "12") (pinfunction "P0_6_12") (pintype "bidirectional"))
    )
    (net (code "62") (name "unconnected-(J1-SBU1-PadA8)") (class "Default")
      (node (ref "J1") (pin "A8") (pinfunction "SBU1_A8") (pintype "bidirectional"))
    )
    (net (code "63") (name "unconnected-(J1-SBU2-PadB8)") (class "Default")
      (node (ref "J1") (pin "B8") (pinfunction "SBU2_B8") (pintype "bidirectional"))
    )
    (net (code "64") (name "unconnected-(R2-Pad1)") (class "Default")
      (node (ref "R2") (pin "1") (pinfunction "1_1") (pintype "passive"))
    )
    (net (code "65") (name "unconnected-(U$5-FSPICS0-LO_SCK-G10-Pad14)") (class "Default")
      (node (ref "U$5") (pin "14") (pinfunction "FSPICS0-LO_SCK-G10_14") (pintype "bidirectional"))
    )
    (net (code "66") (name "unconnected-(U$5-G3-A1.3-LORA_DIO1-Pad7)") (class "Default")
      (node (ref "U$5") (pin "7") (pinfunction "G3-A1.3-LORA_DIO1_7") (pintype "bidirectional"))
    )
    (net (code "67") (name "unconnected-(U$5-G4-A1.4-LO_BY-MTMS-FSPIHD-Pad6)") (class "Default")
      (node (ref "U$5") (pin "6") (pinfunction "G4-A1.4-LO_BY-MTMS-FSPIHD_6") (pintype "bidirectional"))
    )
    (net (code "68") (name "unconnected-(U$5-G5-A2.0-LO_RST-MTDI-FSPIWP-Pad5)") (class "Default")
      (node (ref "U$5") (pin "5") (pinfunction "G5-A2.0-LO_RST-MTDI-FSPIWP_5") (pintype "bidirectional"))
    )
    (net (code "69") (name "unconnected-(U$5-G6-LO_MI-MTCK-FSPICK-Pad4)") (class "Default")
      (node (ref "U$5") (pin "4") (pinfunction "G6-LO_MI-MTCK-FSPICK_4") (pintype "bidirectional"))
    )
    (net (code "70") (name "unconnected-(U$5-G7-LO_MO-MTDO-FSPID-Pad3)") (class "Default")
      (node (ref "U$5") (pin "3") (pinfunction "G7-LO_MO-MTDO-FSPID_3") (pintype "bidirectional"))
    )
    (net (code "71") (name "unconnected-(U$5-LORA_ANT-Pad22)") (class "Default")
      (node (ref "U$5") (pin "22") (pinfunction "LORA_ANT_22") (pintype "bidirectional"))
    )
    (net (code "72") (name "unconnected-(U$5-LO_NSS-G8-Pad16)") (class "Default")
      (node (ref "U$5") (pin "16") (pinfunction "LO_NSS-G8_16") (pintype "bidirectional"))
    )
  )
)
